# dl380_fan_mod.net
KiCad netlist of a schematic drawn in Altium Designer
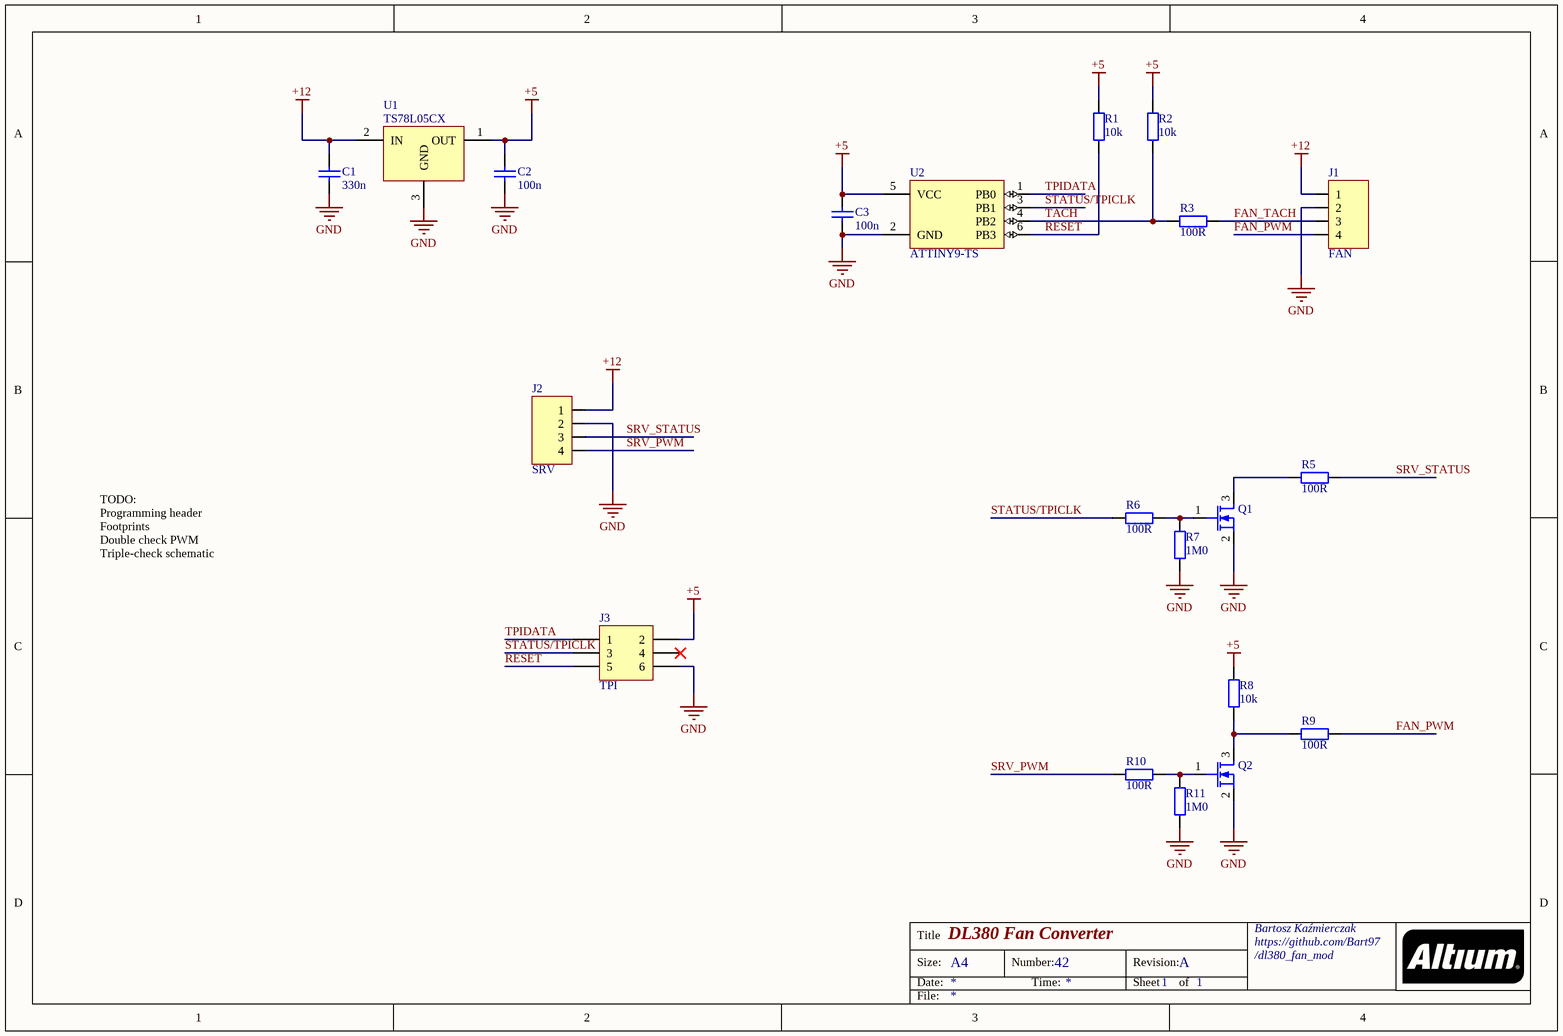
[diagram p0: dl380_fan_mod.SchDoc]

(export (version "E")
  (design (tool "Eeschema 10.0.6"))
  (components
    (comp (ref "C1")
      (value "330n")
      (footprint "CAPC320X160X180L55N")
      (description "Capacitor SMD 1206, 330n")
      (libsource (lib "Passives") (part "Capacitor"))
    )
    (comp (ref "C2")
      (value "100n")
      (footprint "CAPC1608X08N")
      (description "Capacitor SMD 0603, 100n")
      (libsource (lib "Passives") (part "Capacitor"))
    )
    (comp (ref "C3")
      (value "100n")
      (footprint "CAPC1608X08N")
      (description "Capacitor SMD 0603, 100n")
      (libsource (lib "Passives") (part "Capacitor"))
    )
    (comp (ref "J1")
      (value "FAN")
      (footprint "4x_PAD_4x1")
      (description "4x_PAD_4x1")
      (libsource (lib "") (part "Generic 1X4_1"))
    )
    (comp (ref "J2")
      (value "SRV")
      (footprint "4x_PAD_4x1")
      (description "4x_PAD_4x1")
      (libsource (lib "Components") (part "Generic 1X4"))
    )
    (comp (ref "J3")
      (value "TPI")
      (footprint "HDRV6W40P127_3X2_381X340H570")
      (description "2x3 Pin Header, 50mil, 1.27mm, THT")
      (libsource (lib "Components") (part "Generic 2X3"))
    )
    (comp (ref "Q1")
      (value "MOSFET-N")
      (footprint "SOT23-3P95_230X110L30X43N")
      (description "20V N-channel MOSFET, SOT-23")
      (fields (field (name "MANUFACTURER") "Nexperia") (field (name "PART NUMBER") "PMV30UN2"))
      (libsource (lib "Components") (part "MOSFET-N G1 S2 D3"))
    )
    (comp (ref "Q2")
      (value "MOSFET-N")
      (footprint "SOT23-3P95_230X110L30X43N")
      (description "20V N-channel MOSFET, SOT-23")
      (fields (field (name "MANUFACTURER") "Nexperia") (field (name "PART NUMBER") "PMV30UN2"))
      (libsource (lib "Components") (part "MOSFET-N G1 S2 D3"))
    )
    (comp (ref "R1")
      (value "10k")
      (footprint "RESC1608X06N")
      (description "Resistor, SMD 0603, 10k, 5%")
      (fields (field (name "TOLERANCE") "5%"))
      (libsource (lib "") (part "Resistor_1"))
    )
    (comp (ref "R2")
      (value "10k")
      (footprint "RESC1608X06N")
      (description "Resistor, SMD 0603, 10k, 5%")
      (fields (field (name "TOLERANCE") "5%"))
      (libsource (lib "") (part "Resistor_1"))
    )
    (comp (ref "R3")
      (value "100R")
      (footprint "RESC1608X06N")
      (description "Resistor, SMD 0603, 100R, 5%")
      (fields (field (name "TOLERANCE") "5%"))
      (libsource (lib "Passives") (part "Resistor"))
    )
    (comp (ref "R5")
      (value "100R")
      (footprint "RESC1608X06N")
      (description "Resistor, SMD 0603, 100R, 5%")
      (fields (field (name "TOLERANCE") "5%"))
      (libsource (lib "Passives") (part "Resistor"))
    )
    (comp (ref "R6")
      (value "100R")
      (footprint "RESC1608X06N")
      (description "Resistor, SMD 0603, 100R, 5%")
      (fields (field (name "TOLERANCE") "5%"))
      (libsource (lib "Passives") (part "Resistor"))
    )
    (comp (ref "R7")
      (value "1M0")
      (footprint "RESC1608X06N")
      (description "Resistor, SMD 0603, 1M0, 5%")
      (fields (field (name "TOLERANCE") "5%"))
      (libsource (lib "") (part "Resistor_1"))
    )
    (comp (ref "R8")
      (value "10k")
      (footprint "RESC1608X06N")
      (description "Resistor, SMD 0603, 10k, 5%")
      (fields (field (name "TOLERANCE") "5%"))
      (libsource (lib "") (part "Resistor_2"))
    )
    (comp (ref "R9")
      (value "100R")
      (footprint "RESC1608X06N")
      (description "Resistor, SMD 0603, 100R, 5%")
      (fields (field (name "TOLERANCE") "5%"))
      (libsource (lib "Passives") (part "Resistor"))
    )
    (comp (ref "R10")
      (value "100R")
      (footprint "RESC1608X06N")
      (description "Resistor, SMD 0603, 100R, 5%")
      (fields (field (name "TOLERANCE") "5%"))
      (libsource (lib "Passives") (part "Resistor"))
    )
    (comp (ref "R11")
      (value "1M0")
      (footprint "RESC1608X06N")
      (description "Resistor, SMD 0603, 1M0, 5%")
      (fields (field (name "TOLERANCE") "5%"))
      (libsource (lib "") (part "Resistor_1"))
    )
    (comp (ref "U1")
      (value "TS78L05CX")
      (footprint "SOT23-3P95_275X135L45X40N")
      (description "5V, 100mA Positive Voltage Regulator")
      (fields (field (name "MANUFACTURER") "Taiwan Semiconductor"))
      (libsource (lib "Components") (part "TS78LxxCX"))
    )
    (comp (ref "U2")
      (value "ATTINY9-TS")
      (footprint "SOT23-6P95_280X145L42X40N")
      (description "Low Power 8-bit ARM Microcontroller with 4 GPIO pins in SOT23-6 package")
      (fields (field (name "MANUFACTURER") "Microchip"))
      (libsource (lib "Components") (part "ATTINY9-TS"))
    )
  )
  (nets
    (net (code "1") (name "+5") (class "Default")
      (node (ref "C2") (pin "2") (pinfunction "2_2") (pintype "passive"))
      (node (ref "C3") (pin "2") (pinfunction "2_2") (pintype "passive"))
      (node (ref "J3") (pin "2") (pinfunction "2_2") (pintype "passive"))
      (node (ref "R1") (pin "2") (pinfunction "2_2") (pintype "passive"))
      (node (ref "R2") (pin "2") (pinfunction "2_2") (pintype "passive"))
      (node (ref "R8") (pin "1") (pinfunction "1_1") (pintype "passive"))
      (node (ref "U1") (pin "1") (pinfunction "OUT_1") (pintype "power_in"))
      (node (ref "U2") (pin "5") (pinfunction "VCC_5") (pintype "power_in"))
    )
    (net (code "2") (name "+12") (class "Default")
      (node (ref "C1") (pin "2") (pinfunction "2_2") (pintype "passive"))
      (node (ref "J1") (pin "1") (pinfunction "1_1") (pintype "passive"))
      (node (ref "J2") (pin "1") (pinfunction "1_1") (pintype "passive"))
      (node (ref "U1") (pin "2") (pinfunction "IN_2") (pintype "power_in"))
    )
    (net (code "3") (name "/FAN_PWM") (class "Default")
      (node (ref "J1") (pin "4") (pinfunction "4_4") (pintype "passive"))
      (node (ref "R9") (pin "1") (pinfunction "1_1") (pintype "passive"))
    )
    (net (code "4") (name "/FAN_TACH") (class "Default")
      (node (ref "J1") (pin "3") (pinfunction "3_3") (pintype "passive"))
      (node (ref "R3") (pin "1") (pinfunction "1_1") (pintype "passive"))
    )
    (net (code "5") (name "/RESET") (class "Default")
      (node (ref "J3") (pin "5") (pinfunction "5_5") (pintype "passive"))
      (node (ref "R1") (pin "1") (pinfunction "1_1") (pintype "passive"))
      (node (ref "U2") (pin "6") (pinfunction "PB3_6") (pintype "bidirectional"))
    )
    (net (code "6") (name "/SRV_PWM") (class "Default")
      (node (ref "J2") (pin "4") (pinfunction "4_4") (pintype "passive"))
      (node (ref "R10") (pin "2") (pinfunction "2_2") (pintype "passive"))
    )
    (net (code "7") (name "/SRV_STATUS") (class "Default")
      (node (ref "J2") (pin "3") (pinfunction "3_3") (pintype "passive"))
      (node (ref "R5") (pin "1") (pinfunction "1_1") (pintype "passive"))
    )
    (net (code "8") (name "/STATUS{slash}TPICLK") (class "Default")
      (node (ref "J3") (pin "3") (pinfunction "3_3") (pintype "passive"))
      (node (ref "R6") (pin "2") (pinfunction "2_2") (pintype "passive"))
      (node (ref "U2") (pin "3") (pinfunction "PB1_3") (pintype "bidirectional"))
    )
    (net (code "9") (name "/TACH") (class "Default")
      (node (ref "R2") (pin "1") (pinfunction "1_1") (pintype "passive"))
      (node (ref "R3") (pin "2") (pinfunction "2_2") (pintype "passive"))
      (node (ref "U2") (pin "4") (pinfunction "PB2_4") (pintype "bidirectional"))
    )
    (net (code "10") (name "/TPIDATA") (class "Default")
      (node (ref "J3") (pin "1") (pinfunction "1_1") (pintype "passive"))
      (node (ref "U2") (pin "1") (pinfunction "PB0_1") (pintype "bidirectional"))
    )
    (net (code "11") (name "GND") (class "Default")
      (node (ref "C1") (pin "1") (pinfunction "1_1") (pintype "passive"))
      (node (ref "C2") (pin "1") (pinfunction "1_1") (pintype "passive"))
      (node (ref "C3") (pin "1") (pinfunction "1_1") (pintype "passive"))
      (node (ref "J1") (pin "2") (pinfunction "2_2") (pintype "passive"))
      (node (ref "J2") (pin "2") (pinfunction "2_2") (pintype "passive"))
      (node (ref "J3") (pin "6") (pinfunction "6_6") (pintype "passive"))
      (node (ref "Q1") (pin "2") (pinfunction "S_2") (pintype "passive"))
      (node (ref "Q2") (pin "2") (pinfunction "S_2") (pintype "passive"))
      (node (ref "R11") (pin "1") (pinfunction "1_1") (pintype "passive"))
      (node (ref "R7") (pin "1") (pinfunction "1_1") (pintype "passive"))
      (node (ref "U1") (pin "3") (pinfunction "GND_3") (pintype "power_in"))
      (node (ref "U2") (pin "2") (pinfunction "GND_2") (pintype "passive"))
    )
    (net (code "12") (name "Net-(Q1-D)") (class "Default")
      (node (ref "Q1") (pin "3") (pinfunction "D_3") (pintype "passive"))
      (node (ref "R5") (pin "2") (pinfunction "2_2") (pintype "passive"))
    )
    (net (code "13") (name "Net-(Q1-G)") (class "Default")
      (node (ref "Q1") (pin "1") (pinfunction "G_1") (pintype "passive"))
      (node (ref "R6") (pin "1") (pinfunction "1_1") (pintype "passive"))
      (node (ref "R7") (pin "2") (pinfunction "2_2") (pintype "passive"))
    )
    (net (code "14") (name "Net-(Q2-D)") (class "Default")
      (node (ref "Q2") (pin "3") (pinfunction "D_3") (pintype "passive"))
      (node (ref "R8") (pin "2") (pinfunction "2_2") (pintype "passive"))
      (node (ref "R9") (pin "2") (pinfunction "2_2") (pintype "passive"))
    )
    (net (code "15") (name "Net-(Q2-G)") (class "Default")
      (node (ref "Q2") (pin "1") (pinfunction "G_1") (pintype "passive"))
      (node (ref "R10") (pin "1") (pinfunction "1_1") (pintype "passive"))
      (node (ref "R11") (pin "2") (pinfunction "2_2") (pintype "passive"))
    )
    (net (code "16") (name "unconnected-(J3-Pad4)") (class "Default")
      (node (ref "J3") (pin "4") (pinfunction "4_4") (pintype "passive+no_connect"))
    )
  )
)
